# MRCS-SIGNAL-COMMON-DISTRIBUTION.net
KiCad netlist of a schematic drawn in EAGLE
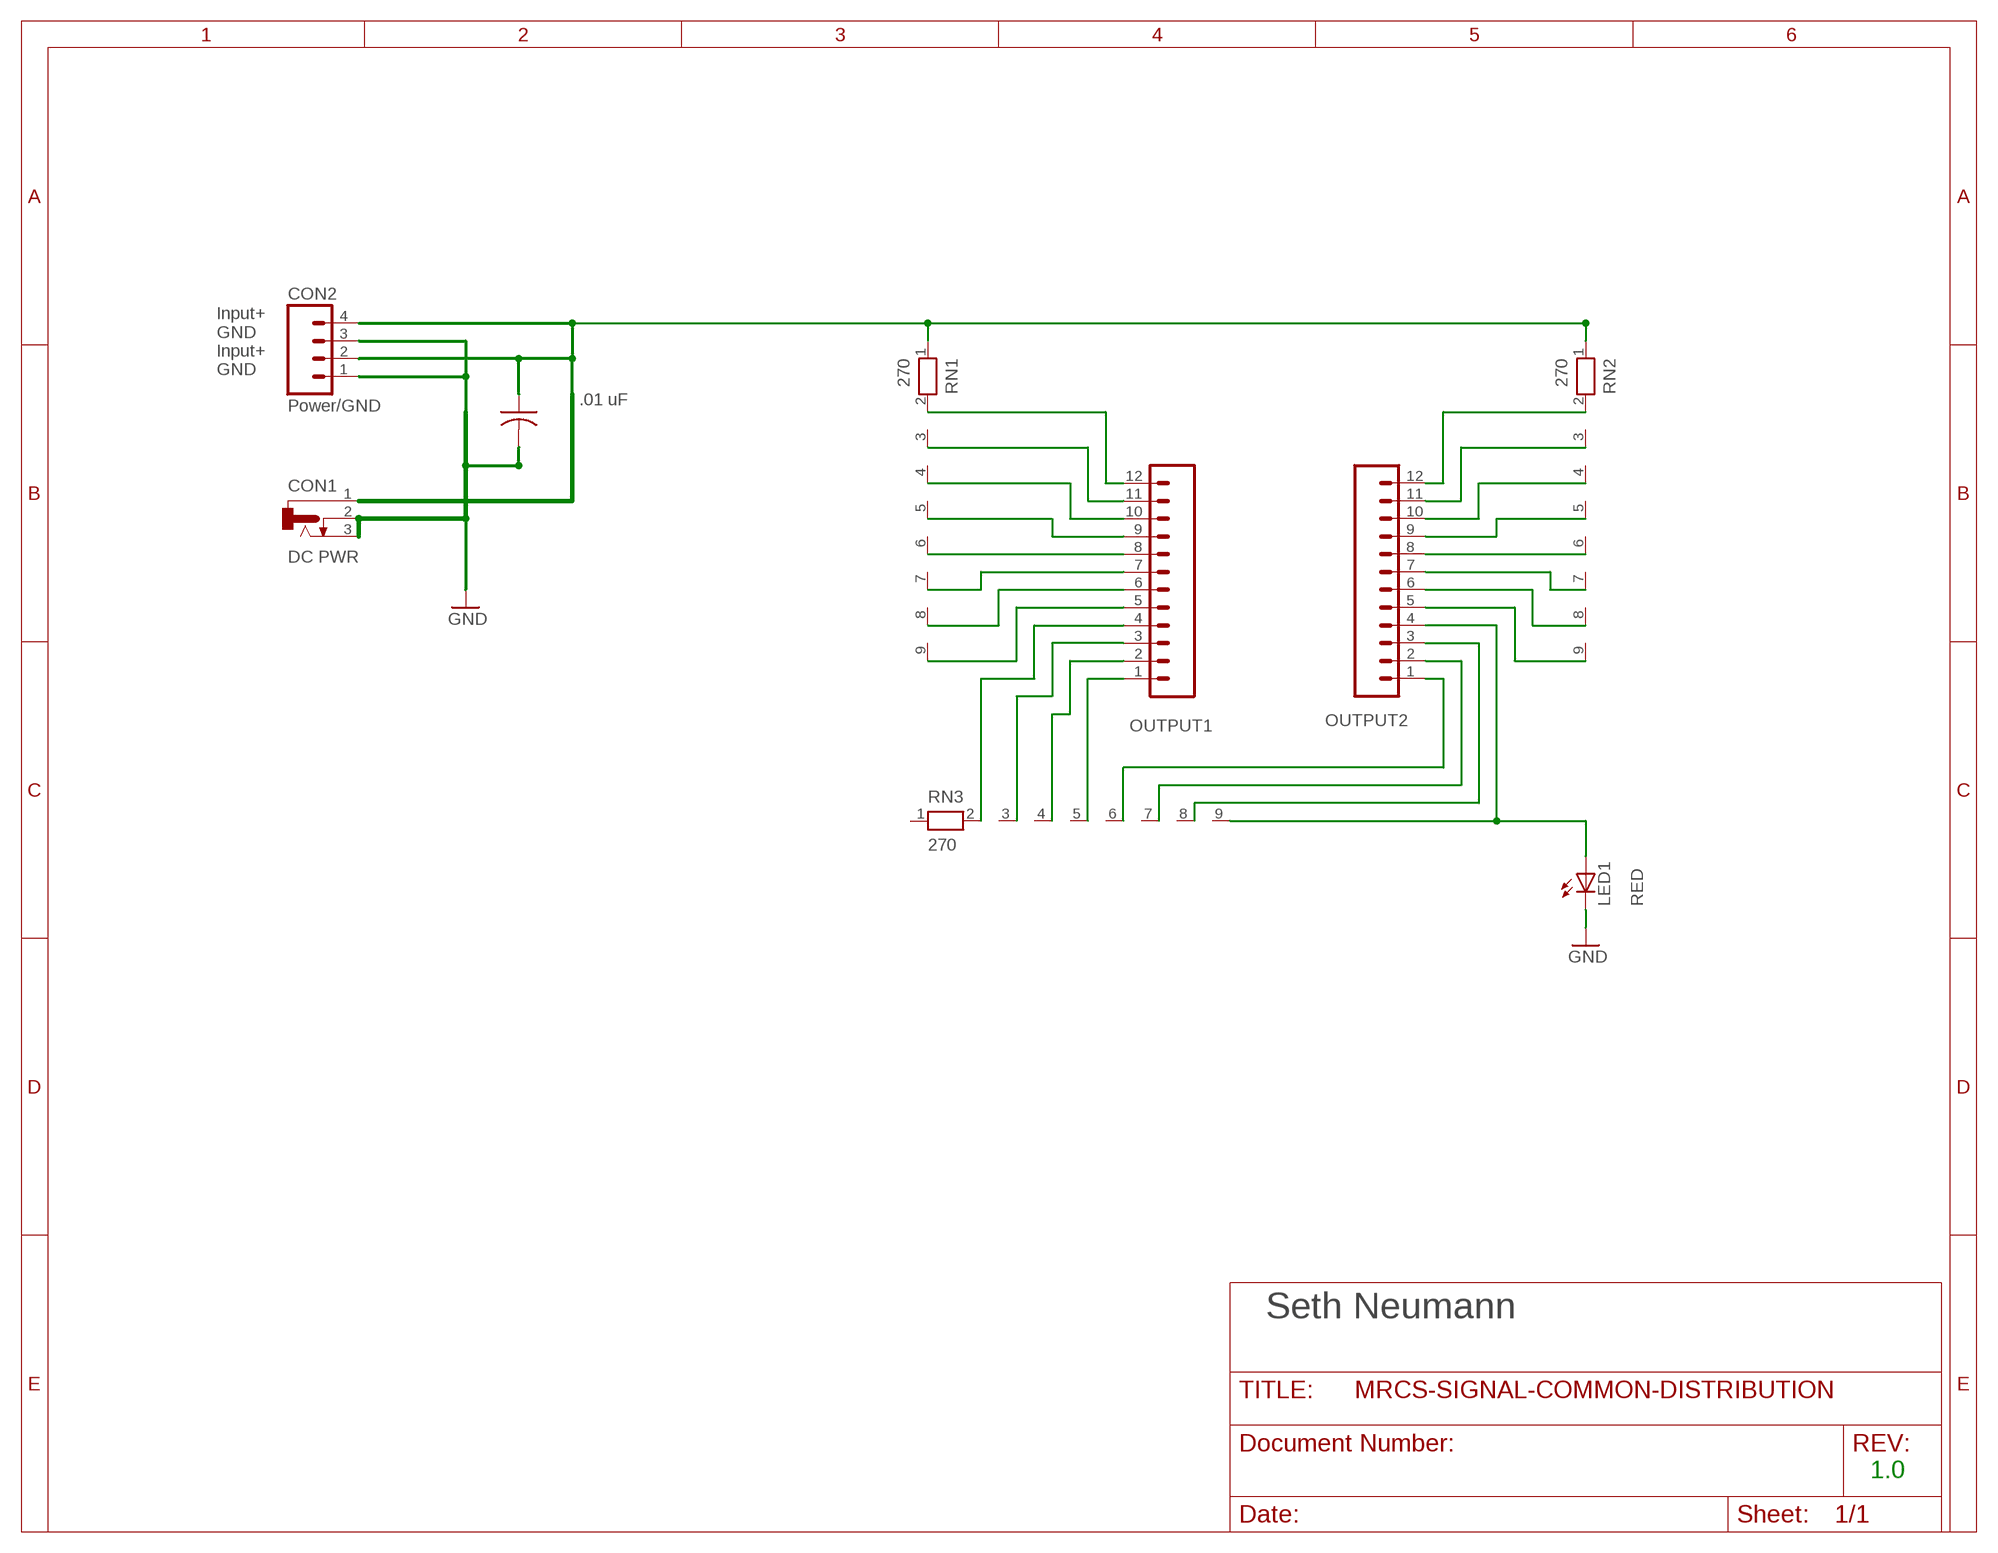
[diagram p0: schematic, sheet 1]

(export (version "E")
  (design (tool "Eeschema 10.0.6"))
  (components
    (comp (ref "C1")
      (value ".01 uF")
      (footprint "eagle-import:C050-024X044")
      (libsource (lib "eagle-import") (part "CAPPTH1"))
    )
    (comp (ref "CON1")
      (value "DC PWR")
      (footprint "eagle-import:DCJ0202")
      (libsource (lib "eagle-import") (part "CONNECTOR-DC-POWER-RA"))
    )
    (comp (ref "CON2")
      (value "Power/GND")
      (footprint "eagle-import:SCREWTERMINAL-3.5MM-4_LOCK")
      (libsource (lib "eagle-import") (part "CONNECTOR-M04SCREW_LOCK"))
    )
    (comp (ref "CON3")
      (value "OUTPUT1")
      (footprint "eagle-import:1X12_LOCK")
      (libsource (lib "eagle-import") (part "CONNECTOR-M12LOCK"))
    )
    (comp (ref "CON4")
      (value "OUTPUT2")
      (footprint "eagle-import:1X12_LOCK")
      (libsource (lib "eagle-import") (part "CONNECTOR-M12LOCK"))
    )
    (comp (ref "LED1")
      (value "RED")
      (footprint "eagle-import:LED3MM")
      (libsource (lib "eagle-import") (part "LEDLED3MM"))
    )
    (comp (ref "RN1")
      (value "270")
      (footprint "eagle-import:RN-9")
      (libsource (lib "eagle-import") (part "RN08"))
    )
    (comp (ref "RN2")
      (value "270")
      (footprint "eagle-import:RN-9")
      (libsource (lib "eagle-import") (part "RN08"))
    )
    (comp (ref "RN3")
      (value "270")
      (footprint "eagle-import:RN-9")
      (libsource (lib "eagle-import") (part "RN08"))
    )
  )
  (nets
    (net (code "1") (name "GND") (class "Default")
      (node (ref "C1") (pin "2") (pinfunction "2_2") (pintype "passive"))
      (node (ref "CON1") (pin "2") (pinfunction "2_2") (pintype "passive"))
      (node (ref "CON1") (pin "3") (pinfunction "3_3") (pintype "passive"))
      (node (ref "CON2") (pin "1") (pinfunction "1_1") (pintype "passive"))
      (node (ref "CON2") (pin "3") (pinfunction "3_3") (pintype "passive"))
      (node (ref "LED1") (pin "K") (pinfunction "C_K") (pintype "passive"))
    )
    (net (code "2") (name "Net-(C1-Pad1)") (class "Default")
      (node (ref "C1") (pin "1") (pinfunction "1_1") (pintype "passive"))
      (node (ref "CON1") (pin "1") (pinfunction "1_1") (pintype "passive"))
      (node (ref "CON2") (pin "2") (pinfunction "2_2") (pintype "passive"))
      (node (ref "CON2") (pin "4") (pinfunction "4_4") (pintype "passive"))
      (node (ref "RN1") (pin "1") (pinfunction "1_1") (pintype "passive"))
      (node (ref "RN2") (pin "1") (pinfunction "1_1") (pintype "passive"))
    )
    (net (code "3") (name "Net-(CON3-Pad1)") (class "Default")
      (node (ref "CON3") (pin "1") (pinfunction "1_1") (pintype "passive"))
      (node (ref "RN3") (pin "5") (pinfunction "5_5") (pintype "passive"))
    )
    (net (code "4") (name "Net-(CON3-Pad2)") (class "Default")
      (node (ref "CON3") (pin "2") (pinfunction "2_2") (pintype "passive"))
      (node (ref "RN3") (pin "4") (pinfunction "4_4") (pintype "passive"))
    )
    (net (code "5") (name "Net-(CON3-Pad3)") (class "Default")
      (node (ref "CON3") (pin "3") (pinfunction "3_3") (pintype "passive"))
      (node (ref "RN3") (pin "3") (pinfunction "3_3") (pintype "passive"))
    )
    (net (code "6") (name "Net-(CON3-Pad4)") (class "Default")
      (node (ref "CON3") (pin "4") (pinfunction "4_4") (pintype "passive"))
      (node (ref "RN3") (pin "2") (pinfunction "2_2") (pintype "passive"))
    )
    (net (code "7") (name "Net-(CON3-Pad5)") (class "Default")
      (node (ref "CON3") (pin "5") (pinfunction "5_5") (pintype "passive"))
      (node (ref "RN1") (pin "9") (pinfunction "9_9") (pintype "passive"))
    )
    (net (code "8") (name "Net-(CON3-Pad6)") (class "Default")
      (node (ref "CON3") (pin "6") (pinfunction "6_6") (pintype "passive"))
      (node (ref "RN1") (pin "8") (pinfunction "8_8") (pintype "passive"))
    )
    (net (code "9") (name "Net-(CON3-Pad7)") (class "Default")
      (node (ref "CON3") (pin "7") (pinfunction "7_7") (pintype "passive"))
      (node (ref "RN1") (pin "7") (pinfunction "7_7") (pintype "passive"))
    )
    (net (code "10") (name "Net-(CON3-Pad8)") (class "Default")
      (node (ref "CON3") (pin "8") (pinfunction "8_8") (pintype "passive"))
      (node (ref "RN1") (pin "6") (pinfunction "6_6") (pintype "passive"))
    )
    (net (code "11") (name "Net-(CON3-Pad9)") (class "Default")
      (node (ref "CON3") (pin "9") (pinfunction "9_9") (pintype "passive"))
      (node (ref "RN1") (pin "5") (pinfunction "5_5") (pintype "passive"))
    )
    (net (code "12") (name "Net-(CON3-Pad10)") (class "Default")
      (node (ref "CON3") (pin "10") (pinfunction "10_10") (pintype "passive"))
      (node (ref "RN1") (pin "4") (pinfunction "4_4") (pintype "passive"))
    )
    (net (code "13") (name "Net-(CON3-Pad11)") (class "Default")
      (node (ref "CON3") (pin "11") (pinfunction "11_11") (pintype "passive"))
      (node (ref "RN1") (pin "3") (pinfunction "3_3") (pintype "passive"))
    )
    (net (code "14") (name "Net-(CON3-Pad12)") (class "Default")
      (node (ref "CON3") (pin "12") (pinfunction "12_12") (pintype "passive"))
      (node (ref "RN1") (pin "2") (pinfunction "2_2") (pintype "passive"))
    )
    (net (code "15") (name "Net-(CON4-Pad1)") (class "Default")
      (node (ref "CON4") (pin "1") (pinfunction "1_1") (pintype "passive"))
      (node (ref "RN3") (pin "6") (pinfunction "6_6") (pintype "passive"))
    )
    (net (code "16") (name "Net-(CON4-Pad2)") (class "Default")
      (node (ref "CON4") (pin "2") (pinfunction "2_2") (pintype "passive"))
      (node (ref "RN3") (pin "7") (pinfunction "7_7") (pintype "passive"))
    )
    (net (code "17") (name "Net-(CON4-Pad3)") (class "Default")
      (node (ref "CON4") (pin "3") (pinfunction "3_3") (pintype "passive"))
      (node (ref "RN3") (pin "8") (pinfunction "8_8") (pintype "passive"))
    )
    (net (code "18") (name "Net-(CON4-Pad4)") (class "Default")
      (node (ref "CON4") (pin "4") (pinfunction "4_4") (pintype "passive"))
      (node (ref "LED1") (pin "A") (pinfunction "A_A") (pintype "passive"))
      (node (ref "RN3") (pin "9") (pinfunction "9_9") (pintype "passive"))
    )
    (net (code "19") (name "Net-(CON4-Pad5)") (class "Default")
      (node (ref "CON4") (pin "5") (pinfunction "5_5") (pintype "passive"))
      (node (ref "RN2") (pin "9") (pinfunction "9_9") (pintype "passive"))
    )
    (net (code "20") (name "Net-(CON4-Pad6)") (class "Default")
      (node (ref "CON4") (pin "6") (pinfunction "6_6") (pintype "passive"))
      (node (ref "RN2") (pin "8") (pinfunction "8_8") (pintype "passive"))
    )
    (net (code "21") (name "Net-(CON4-Pad7)") (class "Default")
      (node (ref "CON4") (pin "7") (pinfunction "7_7") (pintype "passive"))
      (node (ref "RN2") (pin "7") (pinfunction "7_7") (pintype "passive"))
    )
    (net (code "22") (name "Net-(CON4-Pad8)") (class "Default")
      (node (ref "CON4") (pin "8") (pinfunction "8_8") (pintype "passive"))
      (node (ref "RN2") (pin "6") (pinfunction "6_6") (pintype "passive"))
    )
    (net (code "23") (name "Net-(CON4-Pad9)") (class "Default")
      (node (ref "CON4") (pin "9") (pinfunction "9_9") (pintype "passive"))
      (node (ref "RN2") (pin "5") (pinfunction "5_5") (pintype "passive"))
    )
    (net (code "24") (name "Net-(CON4-Pad10)") (class "Default")
      (node (ref "CON4") (pin "10") (pinfunction "10_10") (pintype "passive"))
      (node (ref "RN2") (pin "4") (pinfunction "4_4") (pintype "passive"))
    )
    (net (code "25") (name "Net-(CON4-Pad11)") (class "Default")
      (node (ref "CON4") (pin "11") (pinfunction "11_11") (pintype "passive"))
      (node (ref "RN2") (pin "3") (pinfunction "3_3") (pintype "passive"))
    )
    (net (code "26") (name "Net-(CON4-Pad12)") (class "Default")
      (node (ref "CON4") (pin "12") (pinfunction "12_12") (pintype "passive"))
      (node (ref "RN2") (pin "2") (pinfunction "2_2") (pintype "passive"))
    )
    (net (code "27") (name "unconnected-(RN3-Pad1)") (class "Default")
      (node (ref "RN3") (pin "1") (pinfunction "1_1") (pintype "passive"))
    )
  )
)
